# Schematic.net
KiCad netlist of a schematic drawn in Altium Designer
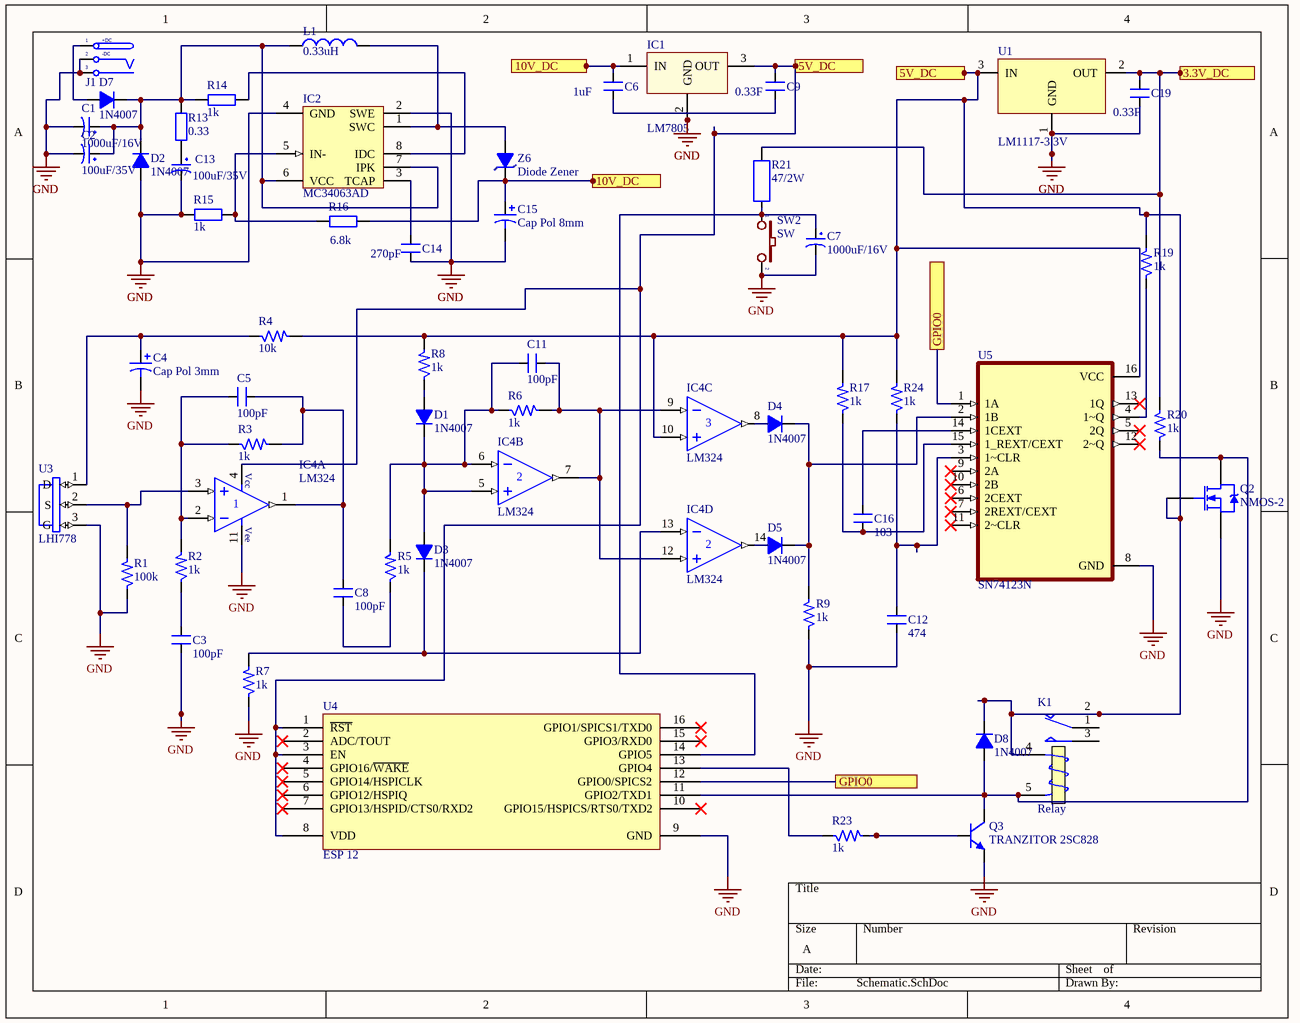
[diagram p0: Schematic.SchDoc]

(export (version "E")
  (design (tool "Eeschema 10.0.6"))
  (components
    (comp (ref "C1")
      (value "1000uF/16V")
      (footprint "CP1.5/3.4")
      (description "Cap 1000uF/16V - 220uF/50V")
      (libsource (lib "syhaunguyen") (part "CP4"))
    )
    (comp (ref "C2")
      (value "100uF/35V")
      (footprint "CP1.5/3.4")
      (description "Cap 100uF/35V - 470uF/16V")
      (libsource (lib "syhaunguyen") (part "CP3"))
    )
    (comp (ref "C3")
      (value "100pF")
      (footprint "CN1")
      (description "Cap np  1pF - 472pF")
      (libsource (lib "syhaunguyen") (part "CN1"))
    )
    (comp (ref "C4")
      (value "Cap Pol 3mm")
      (footprint "C3MM")
      (description "Polarized Capacitor (Axial)")
      (fields (field (name "PUBLISHER") "Altium Limited"))
      (libsource (lib "Cty1") (part "Cap Pol 3mm"))
    )
    (comp (ref "C5")
      (value "100pF")
      (footprint "CN1")
      (description "Cap np  1pF - 472pF")
      (libsource (lib "syhaunguyen") (part "CN1"))
    )
    (comp (ref "C6")
      (value "1uF")
      (footprint "CN1")
      (description "Cap np  1pF - 472pF")
      (libsource (lib "Cty1") (part "CN1"))
    )
    (comp (ref "C7")
      (value "1000uF/16V")
      (footprint "CP1.5/3.4")
      (description "Cap 1000uF/16V - 220uF/50V")
      (libsource (lib "") (part "CP4_1"))
    )
    (comp (ref "C8")
      (value "100pF")
      (footprint "CN1")
      (description "Cap np  1pF - 472pF")
      (libsource (lib "syhaunguyen") (part "CN1"))
    )
    (comp (ref "C9")
      (value "0.33F")
      (footprint "CN1")
      (description "Cap np  1pF - 472pF")
      (libsource (lib "Cty1") (part "CN1"))
    )
    (comp (ref "C11")
      (value "100pF")
      (footprint "CN1")
      (description "Cap np  1pF - 472pF")
      (libsource (lib "syhaunguyen") (part "CN1"))
    )
    (comp (ref "C12")
      (value "474")
      (footprint "CN4")
      (description "Cap np W0.4")
      (libsource (lib "syhaunguyen") (part "CN4"))
    )
    (comp (ref "C13")
      (value "100uF/35V")
      (footprint "CP1.5/3.4")
      (description "Cap 100uF/35V - 470uF/16V")
      (libsource (lib "") (part "CP3_1"))
    )
    (comp (ref "C14")
      (value "270pF")
      (footprint "CN1")
      (description "Cap np  1pF - 472pF")
      (libsource (lib "Cty1") (part "CN1"))
    )
    (comp (ref "C15")
      (value "Cap Pol 8mm")
      (footprint "C10mm")
      (description "Polarized Capacitor (Axial)")
      (fields (field (name "PUBLISHER") "Altium Limited"))
      (libsource (lib "Cty1") (part "Cap Pol 8mm"))
    )
    (comp (ref "C16")
      (value "103")
      (footprint "CN1.5")
      (description "Cap np 682pF => 104pF")
      (libsource (lib "syhaunguyen") (part "CN1.5"))
    )
    (comp (ref "C19")
      (value "0.33F")
      (footprint "CN1")
      (description "Cap np  1pF - 472pF")
      (libsource (lib "Cty1") (part "CN1"))
    )
    (comp (ref "D1")
      (value "1N4007")
      (footprint "D2A")
      (description "Diode 1A")
      (libsource (lib "syhaunguyen") (part "D1A"))
    )
    (comp (ref "D2")
      (value "1N4007")
      (footprint "D1A")
      (description "Diode 1A")
      (libsource (lib "syhaunguyen") (part "D1A"))
    )
    (comp (ref "D3")
      (value "1N4007")
      (footprint "D2A")
      (description "Diode 1A")
      (libsource (lib "syhaunguyen") (part "D1A"))
    )
    (comp (ref "D4")
      (value "1N4007")
      (footprint "D2A")
      (description "Diode 1A")
      (libsource (lib "syhaunguyen") (part "D1A"))
    )
    (comp (ref "D5")
      (value "1N4007")
      (footprint "D2A")
      (description "Diode 1A")
      (libsource (lib "syhaunguyen") (part "D1A"))
    )
    (comp (ref "D7")
      (value "1N4007")
      (footprint "D1A")
      (description "Diode 1A")
      (libsource (lib "syhaunguyen") (part "D1A"))
    )
    (comp (ref "D8")
      (value "1N4007")
      (footprint "D1A")
      (description "Diode 1A")
      (libsource (lib "syhaunguyen") (part "D1A"))
    )
    (comp (ref "IC1")
      (value "LM7805")
      (footprint "QTO-220NH")
      (description "On ap +, from + 5 to + 24VDC")
      (libsource (lib "Cty1") (part "LM78xx"))
    )
    (comp (ref "IC2")
      (value "MC34063AD")
      (footprint "DIP8")
      (description "DC-to-DC Converter Control Circuit")
      (fields (field (name "PUBLISHER") "Altium Limited"))
      (libsource (lib "Cty1") (part "MC34063AD"))
    )
    (comp (ref "IC4")
      (value "LM324")
      (footprint "DIP14")
      (description "Op x 4")
      (libsource (lib "Cty1") (part "LM324"))
    )
    (comp (ref "J1")
      (value "JACK DC 5MM")
      (footprint "JACK DC 5MM")
      (libsource (lib "Cty1") (part "JACK DC 5MM"))
    )
    (comp (ref "K1")
      (value "Relay")
      (footprint "MODULE5B")
      (description "SPDT Relay")
      (fields (field (name "PUBLISHER") "Altium Limited"))
      (libsource (lib "Miscellaneous Devices") (part "Relay"))
    )
    (comp (ref "L1")
      (value "0.33uH")
      (footprint "PCMC063T")
      (description "SMT Power Choke Coil; Size 7.3×6.6×3.0mm, ±20% Tolerance, 0.33uH, 20A")
      (fields (field (name "PUBLISHER") "Altium Limited"))
      (libsource (lib "SSM Inductor") (part "PCMC063T-R33MN"))
    )
    (comp (ref "Q2")
      (value "NMOS-2")
      (footprint "TO-220AB")
      (description "N-Channel Power MOSFET")
      (fields (field (name "PUBLISHER") "Altium Limited"))
      (libsource (lib "Miscellaneous Devices") (part "NMOS-2"))
    )
    (comp (ref "Q3")
      (value "TRANZITOR 2SC828")
      (footprint "TO126")
      (description "NPN General Purpose Amplifier")
      (fields (field (name "PUBLISHER") "Altium Limited"))
      (libsource (lib "Cty1") (part "TRANZITOR 2SC828"))
    )
    (comp (ref "R1")
      (value "100k")
      (footprint "R1/8W")
      (description "Resistor 1/4W")
      (libsource (lib "Devzone_SCHLib") (part "Res"))
    )
    (comp (ref "R2")
      (value "1k")
      (footprint "R1/8W")
      (description "Resistor 1/4W")
      (libsource (lib "syhaunguyen") (part "R"))
    )
    (comp (ref "R3")
      (value "1k")
      (footprint "R1/8W")
      (description "Resistor 1/4W")
      (libsource (lib "syhaunguyen") (part "R"))
    )
    (comp (ref "R4")
      (value "10k")
      (footprint "R1/8W")
      (description "Resistor 1/4W")
      (libsource (lib "Devzone_SCHLib") (part "Res"))
    )
    (comp (ref "R5")
      (value "1k")
      (footprint "R1/8W")
      (description "Resistor 1/4W")
      (libsource (lib "syhaunguyen") (part "R"))
    )
    (comp (ref "R6")
      (value "1k")
      (footprint "R1/8W")
      (description "Resistor 1/4W")
      (libsource (lib "syhaunguyen") (part "R"))
    )
    (comp (ref "R7")
      (value "1k")
      (footprint "R1/8W")
      (description "Resistor 1/4W")
      (libsource (lib "syhaunguyen") (part "R"))
    )
    (comp (ref "R8")
      (value "1k")
      (footprint "R1/8W")
      (description "Resistor 1/4W")
      (libsource (lib "syhaunguyen") (part "R"))
    )
    (comp (ref "R9")
      (value "1k")
      (footprint "R1/8W")
      (description "Resistor 1/4W")
      (libsource (lib "syhaunguyen") (part "R"))
    )
    (comp (ref "R13")
      (value "0.33")
      (footprint "RES-1/4W")
      (description "Resistor R1/4W")
      (libsource (lib "KhanhBK_Library_4") (part "R"))
    )
    (comp (ref "R14")
      (value "1k")
      (footprint "R1/8W")
      (description "Resistor 1/4W")
      (libsource (lib "syhaunguyen") (part "R1/4W"))
    )
    (comp (ref "R15")
      (value "1k")
      (footprint "R1/8W")
      (description "Resistor 1/4W")
      (libsource (lib "syhaunguyen") (part "R1/4W"))
    )
    (comp (ref "R16")
      (value "6.8k")
      (footprint "R1/8W")
      (description "Resistor 1/4W")
      (libsource (lib "Cty1") (part "R1/4W"))
    )
    (comp (ref "R17")
      (value "1k")
      (footprint "R1/8W")
      (description "Resistor 1/4W")
      (libsource (lib "syhaunguyen") (part "R"))
    )
    (comp (ref "R19")
      (value "1k")
      (footprint "R1/8W")
      (description "Resistor 1/4W")
      (libsource (lib "syhaunguyen") (part "R"))
    )
    (comp (ref "R20")
      (value "1k")
      (footprint "R1/4W")
      (description "Resistor 1/4W")
      (libsource (lib "syhaunguyen") (part "R"))
    )
    (comp (ref "R21")
      (value "47/2W")
      (footprint "R2W")
      (description "Resistor 2W")
      (libsource (lib "syhaunguyen") (part "R2W"))
    )
    (comp (ref "R23")
      (value "1k")
      (footprint "R1/4W")
      (description "Resistor 1/4W")
      (libsource (lib "syhaunguyen") (part "R"))
    )
    (comp (ref "R24")
      (value "1k")
      (footprint "R1/8W")
      (description "Resistor 1/4W")
      (libsource (lib "syhaunguyen") (part "R"))
    )
    (comp (ref "SW2")
      (value "SW")
      (footprint "SW2")
      (description "Switch button 2 pin")
      (libsource (lib "Cty1") (part "SW2"))
    )
    (comp (ref "U1")
      (value "LM1117-3.3V")
      (footprint "LM1117-SOP")
      (description "800mA Low-Dropout Linear Regulator")
      (fields (field (name "CREATOR") "Nguyen Ba Bien"))
      (libsource (lib "Cty1") (part "LM1117"))
    )
    (comp (ref "U3")
      (value "LHI778")
      (footprint "SnapEDApcb:SNR3-D8.1XH4.2MM")
      (description "DIP PIR Motion Sensor")
      (fields (field (name "MF") "PerkinElmer Optoelectronics"))
      (libsource (lib "SnapEDAsch") (part "DIP-MOTION/POSITION-LHI778(3P-D8.1MM)"))
    )
    (comp (ref "U4")
      (value "ESP 12")
      (footprint "ESP12")
      (description "ESP-12 Wi-Fi Module by AI-Thinker")
      (libsource (lib "KhanhBK_Library_3") (part "ESP_12"))
    )
    (comp (ref "U5")
      (value "SN74123N")
      (footprint "DIP794W45P254L1969H508Q16:DIP794W45P254L1969H508Q16")
      (libsource (lib "SN74123N") (part "SN74123N"))
    )
    (comp (ref "Z6")
      (value "Diode Zener")
      (footprint "D1A")
      (description "Diode  Zener")
      (libsource (lib "Cty1") (part "Diode Zener"))
    )
  )
  (nets
    (net (code "1") (name "/3.3V_DC") (class "Default")
      (node (ref "C19") (pin "2") (pinfunction "2_2") (pintype "passive"))
      (node (ref "R20") (pin "2") (pinfunction "2_2") (pintype "passive"))
      (node (ref "R21") (pin "2") (pinfunction "2_2") (pintype "passive"))
      (node (ref "U1") (pin "2") (pinfunction "OUT_2") (pintype "passive"))
    )
    (net (code "2") (name "/5V_DC") (class "Default")
      (node (ref "C9") (pin "2") (pinfunction "2_2") (pintype "passive"))
      (node (ref "D8") (pin "2") (pinfunction "K_2") (pintype "passive"))
      (node (ref "IC1") (pin "3") (pinfunction "OUT_3") (pintype "passive"))
      (node (ref "IC4") (pin "10") (pinfunction "IN+_10") (pintype "input"))
      (node (ref "IC4") (pin "4") (pinfunction "V+_4") (pintype "power_in"))
      (node (ref "K1") (pin "2") (pinfunction "NC_2") (pintype "passive"))
      (node (ref "K1") (pin "4") (pinfunction "T1_4") (pintype "passive"))
      (node (ref "Q2") (pin "1") (pinfunction "G_1") (pintype "passive"))
      (node (ref "R17") (pin "2") (pinfunction "2_2") (pintype "passive"))
      (node (ref "R19") (pin "2") (pinfunction "2_2") (pintype "passive"))
      (node (ref "R24") (pin "2") (pinfunction "2_2") (pintype "passive"))
      (node (ref "R4") (pin "2") (pinfunction "2_2") (pintype "passive"))
      (node (ref "R8") (pin "2") (pinfunction "2_2") (pintype "passive"))
      (node (ref "U1") (pin "3") (pinfunction "IN_3") (pintype "passive"))
      (node (ref "U4") (pin "1") (pinfunction "~{RST}_1") (pintype "passive"))
      (node (ref "U4") (pin "3") (pinfunction "EN_3") (pintype "passive"))
      (node (ref "U4") (pin "8") (pinfunction "VDD_8") (pintype "passive"))
      (node (ref "U5") (pin "16") (pinfunction "VCC_16") (pintype "power_in"))
    )
    (net (code "3") (name "/10V_DC") (class "Default")
      (node (ref "C15") (pin "1") (pinfunction "1_1") (pintype "passive"))
      (node (ref "C6") (pin "2") (pinfunction "2_2") (pintype "passive"))
      (node (ref "IC1") (pin "1") (pinfunction "IN_1") (pintype "passive"))
      (node (ref "R16") (pin "2") (pinfunction "2_2") (pintype "passive"))
      (node (ref "Z6") (pin "2") (pinfunction "K_2") (pintype "passive"))
    )
    (net (code "4") (name "/GPIO0") (class "Default")
      (node (ref "U4") (pin "12") (pinfunction "GPIO0/SPICS2_12") (pintype "passive"))
      (node (ref "U5") (pin "1") (pinfunction "1A_1") (pintype "input"))
    )
    (net (code "5") (name "GND") (class "Default")
      (node (ref "C1") (pin "2") (pinfunction "2_2") (pintype "passive"))
      (node (ref "C12") (pin "1") (pinfunction "1_1") (pintype "passive"))
      (node (ref "C13") (pin "2") (pinfunction "2_2") (pintype "passive"))
      (node (ref "C14") (pin "1") (pinfunction "1_1") (pintype "passive"))
      (node (ref "C15") (pin "2") (pinfunction "2_2") (pintype "passive"))
      (node (ref "C19") (pin "1") (pinfunction "1_1") (pintype "passive"))
      (node (ref "C2") (pin "2") (pinfunction "2_2") (pintype "passive"))
      (node (ref "C3") (pin "1") (pinfunction "1_1") (pintype "passive"))
      (node (ref "C4") (pin "2") (pinfunction "2_2") (pintype "passive"))
      (node (ref "C7") (pin "2") (pinfunction "2_2") (pintype "passive"))
      (node (ref "D2") (pin "1") (pinfunction "A_1") (pintype "passive"))
      (node (ref "IC1") (pin "2") (pinfunction "GND_2") (pintype "passive"))
      (node (ref "IC2") (pin "2") (pinfunction "SWE_2") (pintype "passive"))
      (node (ref "IC2") (pin "4") (pinfunction "GND_4") (pintype "power_in"))
      (node (ref "IC4") (pin "11") (pinfunction "V-_11") (pintype "power_in"))
      (node (ref "J1") (pin "2") (pinfunction "TN_2") (pintype "passive"))
      (node (ref "J1") (pin "3") (pinfunction "S_3") (pintype "power_in"))
      (node (ref "Q2") (pin "3") (pinfunction "S_3") (pintype "passive"))
      (node (ref "Q3") (pin "1") (pinfunction "E_1") (pintype "passive"))
      (node (ref "R1") (pin "1") (pinfunction "1_1") (pintype "passive"))
      (node (ref "R15") (pin "1") (pinfunction "1_1") (pintype "passive"))
      (node (ref "R7") (pin "1") (pinfunction "1_1") (pintype "passive"))
      (node (ref "R9") (pin "1") (pinfunction "1_1") (pintype "passive"))
      (node (ref "SW2") (pin "2") (pinfunction "2_2") (pintype "passive"))
      (node (ref "U1") (pin "1") (pinfunction "GND_1") (pintype "passive"))
      (node (ref "U3") (pin "3") (pinfunction "G_3") (pintype "bidirectional"))
      (node (ref "U4") (pin "9") (pinfunction "GND_9") (pintype "passive"))
      (node (ref "U5") (pin "8") (pinfunction "GND_8") (pintype "power_in"))
    )
    (net (code "6") (name "Net-(C3-Pad2)") (class "Default")
      (node (ref "C3") (pin "2") (pinfunction "2_2") (pintype "passive"))
      (node (ref "R2") (pin "1") (pinfunction "1_1") (pintype "passive"))
    )
    (net (code "7") (name "Net-(C6-Pad1)") (class "Default")
      (node (ref "C6") (pin "1") (pinfunction "1_1") (pintype "passive"))
      (node (ref "C9") (pin "1") (pinfunction "1_1") (pintype "passive"))
    )
    (net (code "8") (name "Net-(C8-Pad1)") (class "Default")
      (node (ref "C8") (pin "1") (pinfunction "1_1") (pintype "passive"))
      (node (ref "R5") (pin "1") (pinfunction "1_1") (pintype "passive"))
    )
    (net (code "9") (name "Net-(C13-Pad1)") (class "Default")
      (node (ref "C13") (pin "1") (pinfunction "1_1") (pintype "passive"))
      (node (ref "R13") (pin "1") (pinfunction "1_1") (pintype "passive"))
    )
    (net (code "10") (name "Net-(D1-A)") (class "Default")
      (node (ref "D1") (pin "1") (pinfunction "A_1") (pintype "passive"))
      (node (ref "R8") (pin "1") (pinfunction "1_1") (pintype "passive"))
    )
    (net (code "11") (name "Net-(D1-K)") (class "Default")
      (node (ref "C11") (pin "1") (pinfunction "1_1") (pintype "passive"))
      (node (ref "D1") (pin "2") (pinfunction "K_2") (pintype "passive"))
      (node (ref "D3") (pin "1") (pinfunction "A_1") (pintype "passive"))
      (node (ref "IC4") (pin "5") (pinfunction "IN+_5") (pintype "input"))
      (node (ref "IC4") (pin "6") (pinfunction "IN-_6") (pintype "input"))
      (node (ref "R5") (pin "2") (pinfunction "2_2") (pintype "passive"))
      (node (ref "R6") (pin "1") (pinfunction "1_1") (pintype "passive"))
    )
    (net (code "12") (name "Net-(D2-K)") (class "Default")
      (node (ref "C1") (pin "1") (pinfunction "1_1") (pintype "passive"))
      (node (ref "C2") (pin "1") (pinfunction "1_1") (pintype "passive"))
      (node (ref "D2") (pin "2") (pinfunction "K_2") (pintype "passive"))
      (node (ref "D7") (pin "2") (pinfunction "K_2") (pintype "passive"))
      (node (ref "IC2") (pin "6") (pinfunction "VCC_6") (pintype "power_in"))
      (node (ref "IC2") (pin "7") (pinfunction "IPK_7") (pintype "passive"))
      (node (ref "L1") (pin "1") (pinfunction "1_1") (pintype "passive"))
      (node (ref "R13") (pin "2") (pinfunction "2_2") (pintype "passive"))
      (node (ref "R14") (pin "1") (pinfunction "1_1") (pintype "passive"))
    )
    (net (code "13") (name "Net-(D3-K)") (class "Default")
      (node (ref "D3") (pin "2") (pinfunction "K_2") (pintype "passive"))
      (node (ref "IC4") (pin "13") (pinfunction "IN-_13") (pintype "input"))
      (node (ref "R7") (pin "2") (pinfunction "2_2") (pintype "passive"))
    )
    (net (code "14") (name "Net-(D4-A)") (class "Default")
      (node (ref "D4") (pin "1") (pinfunction "A_1") (pintype "passive"))
      (node (ref "IC4") (pin "8") (pinfunction "OUT_8") (pintype "output"))
    )
    (net (code "15") (name "Net-(D4-K)") (class "Default")
      (node (ref "D4") (pin "2") (pinfunction "K_2") (pintype "passive"))
      (node (ref "D5") (pin "2") (pinfunction "K_2") (pintype "passive"))
      (node (ref "R9") (pin "2") (pinfunction "2_2") (pintype "passive"))
      (node (ref "U5") (pin "2") (pinfunction "1B_2") (pintype "input"))
    )
    (net (code "16") (name "Net-(D5-A)") (class "Default")
      (node (ref "D5") (pin "1") (pinfunction "A_1") (pintype "passive"))
      (node (ref "IC4") (pin "14") (pinfunction "OUT_14") (pintype "output"))
    )
    (net (code "17") (name "Net-(D7-A)") (class "Default")
      (node (ref "D7") (pin "1") (pinfunction "A_1") (pintype "passive"))
      (node (ref "J1") (pin "1") (pinfunction "T_1") (pintype "passive"))
    )
    (net (code "18") (name "Net-(D8-A)") (class "Default")
      (node (ref "D8") (pin "1") (pinfunction "A_1") (pintype "passive"))
      (node (ref "K1") (pin "5") (pinfunction "T2_5") (pintype "passive"))
      (node (ref "Q2") (pin "2") (pinfunction "D_2") (pintype "passive"))
      (node (ref "Q3") (pin "3") (pinfunction "B_3") (pintype "passive"))
      (node (ref "R20") (pin "1") (pinfunction "1_1") (pintype "passive"))
      (node (ref "U4") (pin "11") (pinfunction "GPIO2/TXD1_11") (pintype "passive"))
    )
    (net (code "19") (name "Net-(IC2-IDC)") (class "Default")
      (node (ref "IC2") (pin "8") (pinfunction "IDC_8") (pintype "open_collector"))
      (node (ref "R14") (pin "2") (pinfunction "2_2") (pintype "passive"))
    )
    (net (code "20") (name "Net-(IC2-IN-)") (class "Default")
      (node (ref "IC2") (pin "5") (pinfunction "IN-_5") (pintype "input"))
      (node (ref "R15") (pin "2") (pinfunction "2_2") (pintype "passive"))
      (node (ref "R16") (pin "1") (pinfunction "1_1") (pintype "passive"))
    )
    (net (code "21") (name "Net-(IC2-SWC)") (class "Default")
      (node (ref "IC2") (pin "1") (pinfunction "SWC_1") (pintype "passive"))
      (node (ref "L1") (pin "2") (pinfunction "2_2") (pintype "passive"))
      (node (ref "Z6") (pin "1") (pinfunction "A_1") (pintype "passive"))
    )
    (net (code "22") (name "Net-(IC2-TCAP)") (class "Default")
      (node (ref "C14") (pin "2") (pinfunction "2_2") (pintype "passive"))
      (node (ref "IC2") (pin "3") (pinfunction "TCAP_3") (pintype "passive"))
    )
    (net (code "23") (name "Net-(IC4A-IN+)") (class "Default")
      (node (ref "IC4") (pin "3") (pinfunction "IN+_3") (pintype "input"))
      (node (ref "R1") (pin "2") (pinfunction "2_2") (pintype "passive"))
      (node (ref "U3") (pin "2") (pinfunction "S_2") (pintype "bidirectional"))
    )
    (net (code "24") (name "Net-(IC4A-IN-)") (class "Default")
      (node (ref "C5") (pin "1") (pinfunction "1_1") (pintype "passive"))
      (node (ref "IC4") (pin "2") (pinfunction "IN-_2") (pintype "input"))
      (node (ref "R2") (pin "2") (pinfunction "2_2") (pintype "passive"))
      (node (ref "R3") (pin "1") (pinfunction "1_1") (pintype "passive"))
    )
    (net (code "25") (name "Net-(IC4A-OUT)") (class "Default")
      (node (ref "C5") (pin "2") (pinfunction "2_2") (pintype "passive"))
      (node (ref "C8") (pin "2") (pinfunction "2_2") (pintype "passive"))
      (node (ref "IC4") (pin "1") (pinfunction "OUT_1") (pintype "output"))
      (node (ref "R3") (pin "2") (pinfunction "2_2") (pintype "passive"))
    )
    (net (code "26") (name "Net-(IC4B-OUT)") (class "Default")
      (node (ref "C11") (pin "2") (pinfunction "2_2") (pintype "passive"))
      (node (ref "IC4") (pin "12") (pinfunction "IN+_12") (pintype "input"))
      (node (ref "IC4") (pin "7") (pinfunction "OUT_7") (pintype "output"))
      (node (ref "IC4") (pin "9") (pinfunction "IN-_9") (pintype "input"))
      (node (ref "R6") (pin "2") (pinfunction "2_2") (pintype "passive"))
    )
    (net (code "27") (name "Net-(Q3-C)") (class "Default")
      (node (ref "Q3") (pin "2") (pinfunction "C_2") (pintype "passive"))
      (node (ref "R23") (pin "2") (pinfunction "2_2") (pintype "passive"))
    )
    (net (code "28") (name "Net-(U3-D)") (class "Default")
      (node (ref "C4") (pin "1") (pinfunction "1_1") (pintype "passive"))
      (node (ref "R4") (pin "1") (pinfunction "1_1") (pintype "passive"))
      (node (ref "U3") (pin "1") (pinfunction "D_1") (pintype "bidirectional"))
    )
    (net (code "29") (name "Net-(U4-GPIO4)") (class "Default")
      (node (ref "R23") (pin "1") (pinfunction "1_1") (pintype "passive"))
      (node (ref "U4") (pin "13") (pinfunction "GPIO4_13") (pintype "passive"))
    )
    (net (code "30") (name "Net-(U4-GPIO5)") (class "Default")
      (node (ref "C7") (pin "1") (pinfunction "1_1") (pintype "passive"))
      (node (ref "R21") (pin "1") (pinfunction "1_1") (pintype "passive"))
      (node (ref "SW2") (pin "1") (pinfunction "1_1") (pintype "passive"))
      (node (ref "U4") (pin "14") (pinfunction "GPIO5_14") (pintype "passive"))
    )
    (net (code "31") (name "Net-(U5-1CEXT)") (class "Default")
      (node (ref "C16") (pin "2") (pinfunction "2_2") (pintype "passive"))
      (node (ref "U5") (pin "14") (pinfunction "1CEXT_14") (pintype "input"))
    )
    (net (code "32") (name "Net-(U5-1_REXT{slash}CEXT)") (class "Default")
      (node (ref "C16") (pin "1") (pinfunction "1_1") (pintype "passive"))
      (node (ref "R17") (pin "1") (pinfunction "1_1") (pintype "passive"))
      (node (ref "U5") (pin "15") (pinfunction "1_REXT/CEXT_15") (pintype "input"))
    )
    (net (code "33") (name "Net-(U5-1~CLR)") (class "Default")
      (node (ref "C12") (pin "2") (pinfunction "2_2") (pintype "passive"))
      (node (ref "R24") (pin "1") (pinfunction "1_1") (pintype "passive"))
      (node (ref "U5") (pin "3") (pinfunction "1~CLR_3") (pintype "input"))
    )
    (net (code "34") (name "Net-(U5-1~Q)") (class "Default")
      (node (ref "R19") (pin "1") (pinfunction "1_1") (pintype "passive"))
      (node (ref "U5") (pin "4") (pinfunction "1~Q_4") (pintype "output"))
    )
    (net (code "35") (name "unconnected-(K1-COM-Pad1)") (class "Default")
      (node (ref "K1") (pin "1") (pinfunction "COM_1") (pintype "passive"))
    )
    (net (code "36") (name "unconnected-(K1-NO-Pad3)") (class "Default")
      (node (ref "K1") (pin "3") (pinfunction "NO_3") (pintype "passive"))
    )
    (net (code "37") (name "unconnected-(U4-ADC{slash}TOUT-Pad2)") (class "Default")
      (node (ref "U4") (pin "2") (pinfunction "ADC/TOUT_2") (pintype "passive+no_connect"))
    )
    (net (code "38") (name "unconnected-(U4-GPIO1{slash}SPICS1{slash}TXD0-Pad16)") (class "Default")
      (node (ref "U4") (pin "16") (pinfunction "GPIO1/SPICS1/TXD0_16") (pintype "passive+no_connect"))
    )
    (net (code "39") (name "unconnected-(U4-GPIO3{slash}RXD0-Pad15)") (class "Default")
      (node (ref "U4") (pin "15") (pinfunction "GPIO3/RXD0_15") (pintype "passive+no_connect"))
    )
    (net (code "40") (name "unconnected-(U4-GPIO12{slash}HSPIQ-Pad6)") (class "Default")
      (node (ref "U4") (pin "6") (pinfunction "GPIO12/HSPIQ_6") (pintype "passive+no_connect"))
    )
    (net (code "41") (name "unconnected-(U4-GPIO13{slash}HSPID{slash}CTS0{slash}RXD2-Pad7)") (class "Default")
      (node (ref "U4") (pin "7") (pinfunction "GPIO13/HSPID/CTS0/RXD2_7") (pintype "passive+no_connect"))
    )
    (net (code "42") (name "unconnected-(U4-GPIO14{slash}HSPICLK-Pad5)") (class "Default")
      (node (ref "U4") (pin "5") (pinfunction "GPIO14/HSPICLK_5") (pintype "passive+no_connect"))
    )
    (net (code "43") (name "unconnected-(U4-GPIO15{slash}HSPICS{slash}RTS0{slash}TXD2-Pad10)") (class "Default")
      (node (ref "U4") (pin "10") (pinfunction "GPIO15/HSPICS/RTS0/TXD2_10") (pintype "passive+no_connect"))
    )
    (net (code "44") (name "unconnected-(U4-GPIO16{slash}~{WAKE}-Pad4)") (class "Default")
      (node (ref "U4") (pin "4") (pinfunction "GPIO16/~{WAKE}_4") (pintype "passive+no_connect"))
    )
    (net (code "45") (name "unconnected-(U5-1Q-Pad13)") (class "Default")
      (node (ref "U5") (pin "13") (pinfunction "1Q_13") (pintype "output+no_connect"))
    )
    (net (code "46") (name "unconnected-(U5-2A-Pad9)") (class "Default")
      (node (ref "U5") (pin "9") (pinfunction "2A_9") (pintype "input+no_connect"))
    )
    (net (code "47") (name "unconnected-(U5-2B-Pad10)") (class "Default")
      (node (ref "U5") (pin "10") (pinfunction "2B_10") (pintype "input+no_connect"))
    )
    (net (code "48") (name "unconnected-(U5-2CEXT-Pad6)") (class "Default")
      (node (ref "U5") (pin "6") (pinfunction "2CEXT_6") (pintype "input+no_connect"))
    )
    (net (code "49") (name "unconnected-(U5-2Q-Pad5)") (class "Default")
      (node (ref "U5") (pin "5") (pinfunction "2Q_5") (pintype "output+no_connect"))
    )
    (net (code "50") (name "unconnected-(U5-2REXT{slash}CEXT-Pad7)") (class "Default")
      (node (ref "U5") (pin "7") (pinfunction "2REXT/CEXT_7") (pintype "input+no_connect"))
    )
    (net (code "51") (name "unconnected-(U5-2~CLR-Pad11)") (class "Default")
      (node (ref "U5") (pin "11") (pinfunction "2~CLR_11") (pintype "input+no_connect"))
    )
    (net (code "52") (name "unconnected-(U5-2~Q-Pad12)") (class "Default")
      (node (ref "U5") (pin "12") (pinfunction "2~Q_12") (pintype "output+no_connect"))
    )
  )
)
